# Mako_DSP_USBR1_2.net
KiCad netlist of a schematic drawn in Altium Designer
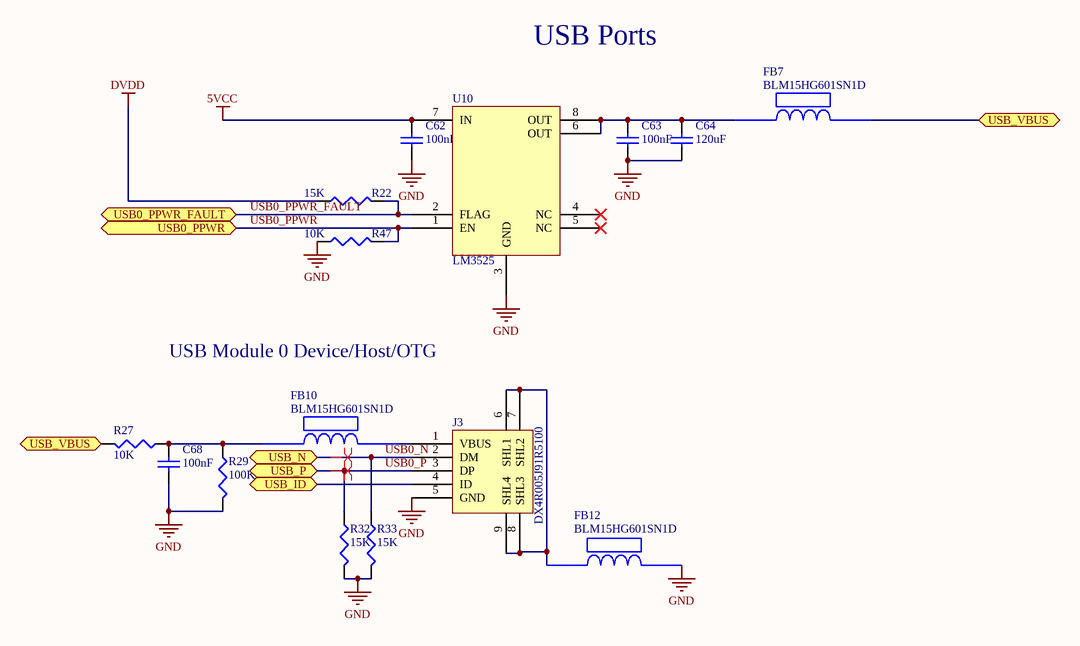
[diagram p0: Mako DSP USBR1.2.SchDoc]

(export (version "E")
  (design (tool "Eeschema 10.0.6"))
  (components
    (comp (ref "C62")
      (value "100nF")
      (footprint "1608[0603]")
      (description "Capacitor (Semiconductor SIM Model)")
      (fields (field (name "Comment") "Cap Semi") (field (name "PUBLISHER") "Altium Limited"))
      (libsource (lib "Miscellaneous Devices") (part "Cap Semi"))
    )
    (comp (ref "C63")
      (value "100nF")
      (footprint "1608[0603]")
      (description "Capacitor (Semiconductor SIM Model)")
      (fields (field (name "Comment") "Cap Semi") (field (name "PUBLISHER") "Altium Limited"))
      (libsource (lib "Miscellaneous Devices") (part "Cap Semi"))
    )
    (comp (ref "C64")
      (value "120uF")
      (footprint "1608[0603]")
      (description "Capacitor (Semiconductor SIM Model)")
      (fields (field (name "Comment") "Cap Semi") (field (name "PUBLISHER") "Altium Limited"))
      (libsource (lib "Miscellaneous Devices") (part "Cap Semi"))
    )
    (comp (ref "C68")
      (value "100nF")
      (footprint "1608[0603]")
      (description "Capacitor (Semiconductor SIM Model)")
      (fields (field (name "Comment") "Cap Semi") (field (name "PUBLISHER") "Altium Limited"))
      (libsource (lib "Miscellaneous Devices") (part "Cap Semi"))
    )
    (comp (ref "FB7")
      (value "BLM15HG601SN1D")
      (footprint "BLM18PG121SN1D")
      (libsource (lib "AHD Part Library") (part "BLM15HG601SN1D"))
    )
    (comp (ref "FB10")
      (value "BLM15HG601SN1D")
      (footprint "BLM18PG121SN1D")
      (libsource (lib "AHD Part Library") (part "BLM15HG601SN1D"))
    )
    (comp (ref "FB12")
      (value "BLM15HG601SN1D")
      (footprint "BLM18PG121SN1D")
      (libsource (lib "AHD Part Library") (part "BLM15HG601SN1D"))
    )
    (comp (ref "J3")
      (value "DX4R005J91R5100")
      (footprint "Micro USB Circular Holes Only")
      (description "Micro USB Jack B")
      (libsource (lib "Adams Altium Library") (part "Micro USB"))
    )
    (comp (ref "R22")
      (value "15K")
      (footprint "J1-0603")
      (description "Resistor")
      (fields (field (name "Comment") "Res3") (field (name "PUBLISHER") "Altium Limited"))
      (libsource (lib "Miscellaneous Devices") (part "Res3"))
    )
    (comp (ref "R27")
      (value "10K")
      (footprint "J1-0603")
      (description "Resistor")
      (fields (field (name "Comment") "Res3") (field (name "PUBLISHER") "Altium Limited"))
      (libsource (lib "Miscellaneous Devices") (part "Res3"))
    )
    (comp (ref "R29")
      (value "100K")
      (footprint "J1-0603")
      (description "Resistor")
      (fields (field (name "Comment") "Res3") (field (name "PUBLISHER") "Altium Limited"))
      (libsource (lib "Miscellaneous Devices") (part "Res3"))
    )
    (comp (ref "R32")
      (value "15K")
      (footprint "J1-0603")
      (description "Resistor")
      (fields (field (name "Comment") "Res3") (field (name "PUBLISHER") "Altium Limited"))
      (libsource (lib "Miscellaneous Devices") (part "Res3"))
    )
    (comp (ref "R33")
      (value "15K")
      (footprint "J1-0603")
      (description "Resistor")
      (fields (field (name "Comment") "Res3") (field (name "PUBLISHER") "Altium Limited"))
      (libsource (lib "Miscellaneous Devices") (part "Res3"))
    )
    (comp (ref "R47")
      (value "10K")
      (footprint "J1-0603")
      (description "Resistor")
      (fields (field (name "Comment") "Res3") (field (name "PUBLISHER") "Altium Limited"))
      (libsource (lib "Miscellaneous Devices") (part "Res3"))
    )
    (comp (ref "U10")
      (value "LM3525")
      (footprint "LM3525")
      (libsource (lib "Adams Altium Library") (part "LM3525"))
    )
  )
  (nets
    (net (code "1") (name "/USB0_N") (class "Default")
      (node (ref "J3") (pin "2") (pinfunction "DM_2") (pintype "passive"))
      (node (ref "R33") (pin "1") (pinfunction "1_1") (pintype "passive"))
    )
    (net (code "2") (name "/USB0_P") (class "Default")
      (node (ref "J3") (pin "3") (pinfunction "DP_3") (pintype "passive"))
      (node (ref "R32") (pin "1") (pinfunction "1_1") (pintype "passive"))
    )
    (net (code "3") (name "/USB0_PPWR") (class "Default")
      (node (ref "R47") (pin "2") (pinfunction "2_2") (pintype "passive"))
      (node (ref "U10") (pin "1") (pinfunction "EN_1") (pintype "passive"))
    )
    (net (code "4") (name "/USB0_PPWR_FAULT") (class "Default")
      (node (ref "R22") (pin "2") (pinfunction "2_2") (pintype "passive"))
      (node (ref "U10") (pin "2") (pinfunction "FLAG_2") (pintype "passive"))
    )
    (net (code "5") (name "/USB_ID") (class "Default")
      (node (ref "J3") (pin "4") (pinfunction "ID_4") (pintype "passive"))
    )
    (net (code "6") (name "/USB_VBUS") (class "Default")
      (node (ref "FB7") (pin "2") (pinfunction "2_2") (pintype "passive"))
      (node (ref "R27") (pin "2") (pinfunction "2_2") (pintype "passive"))
    )
    (net (code "7") (name "5VCC") (class "Default")
      (node (ref "C62") (pin "2") (pinfunction "2_2") (pintype "passive"))
      (node (ref "U10") (pin "7") (pinfunction "IN_7") (pintype "passive"))
    )
    (net (code "8") (name "DVDD") (class "Default")
      (node (ref "R22") (pin "1") (pinfunction "1_1") (pintype "passive"))
    )
    (net (code "9") (name "GND") (class "Default")
      (node (ref "C62") (pin "1") (pinfunction "1_1") (pintype "passive"))
      (node (ref "C63") (pin "1") (pinfunction "1_1") (pintype "passive"))
      (node (ref "C64") (pin "1") (pinfunction "1_1") (pintype "passive"))
      (node (ref "C68") (pin "1") (pinfunction "1_1") (pintype "passive"))
      (node (ref "FB12") (pin "2") (pinfunction "2_2") (pintype "passive"))
      (node (ref "J3") (pin "5") (pinfunction "GND_5") (pintype "passive"))
      (node (ref "R29") (pin "2") (pinfunction "2_2") (pintype "passive"))
      (node (ref "R32") (pin "2") (pinfunction "2_2") (pintype "passive"))
      (node (ref "R33") (pin "2") (pinfunction "2_2") (pintype "passive"))
      (node (ref "R47") (pin "1") (pinfunction "1_1") (pintype "passive"))
      (node (ref "U10") (pin "3") (pinfunction "GND_3") (pintype "passive"))
    )
    (net (code "10") (name "Net-(C63-Pad2)") (class "Default")
      (node (ref "C63") (pin "2") (pinfunction "2_2") (pintype "passive"))
      (node (ref "C64") (pin "2") (pinfunction "2_2") (pintype "passive"))
      (node (ref "FB7") (pin "1") (pinfunction "1_1") (pintype "passive"))
      (node (ref "U10") (pin "6") (pinfunction "OUT_6") (pintype "passive"))
      (node (ref "U10") (pin "8") (pinfunction "OUT_8") (pintype "passive"))
    )
    (net (code "11") (name "Net-(C68-Pad2)") (class "Default")
      (node (ref "C68") (pin "2") (pinfunction "2_2") (pintype "passive"))
      (node (ref "FB10") (pin "1") (pinfunction "1_1") (pintype "passive"))
      (node (ref "R27") (pin "1") (pinfunction "1_1") (pintype "passive"))
      (node (ref "R29") (pin "1") (pinfunction "1_1") (pintype "passive"))
    )
    (net (code "12") (name "Net-(J3-SHL1)") (class "Default")
      (node (ref "FB12") (pin "1") (pinfunction "1_1") (pintype "passive"))
      (node (ref "J3") (pin "6") (pinfunction "SHL1_6") (pintype "passive"))
      (node (ref "J3") (pin "7") (pinfunction "SHL2_7") (pintype "passive"))
      (node (ref "J3") (pin "8") (pinfunction "SHL3_8") (pintype "passive"))
      (node (ref "J3") (pin "9") (pinfunction "SHL4_9") (pintype "passive"))
    )
    (net (code "13") (name "Net-(J3-VBUS)") (class "Default")
      (node (ref "FB10") (pin "2") (pinfunction "2_2") (pintype "passive"))
      (node (ref "J3") (pin "1") (pinfunction "VBUS_1") (pintype "passive"))
    )
    (net (code "14") (name "unconnected-(U10-NC-Pad4)") (class "Default")
      (node (ref "U10") (pin "4") (pinfunction "NC_4") (pintype "passive+no_connect"))
    )
    (net (code "15") (name "unconnected-(U10-NC-Pad5)") (class "Default")
      (node (ref "U10") (pin "5") (pinfunction "NC_5") (pintype "passive+no_connect"))
    )
  )
)
